# FT232RL.net
KiCad netlist of a schematic drawn in EAGLE
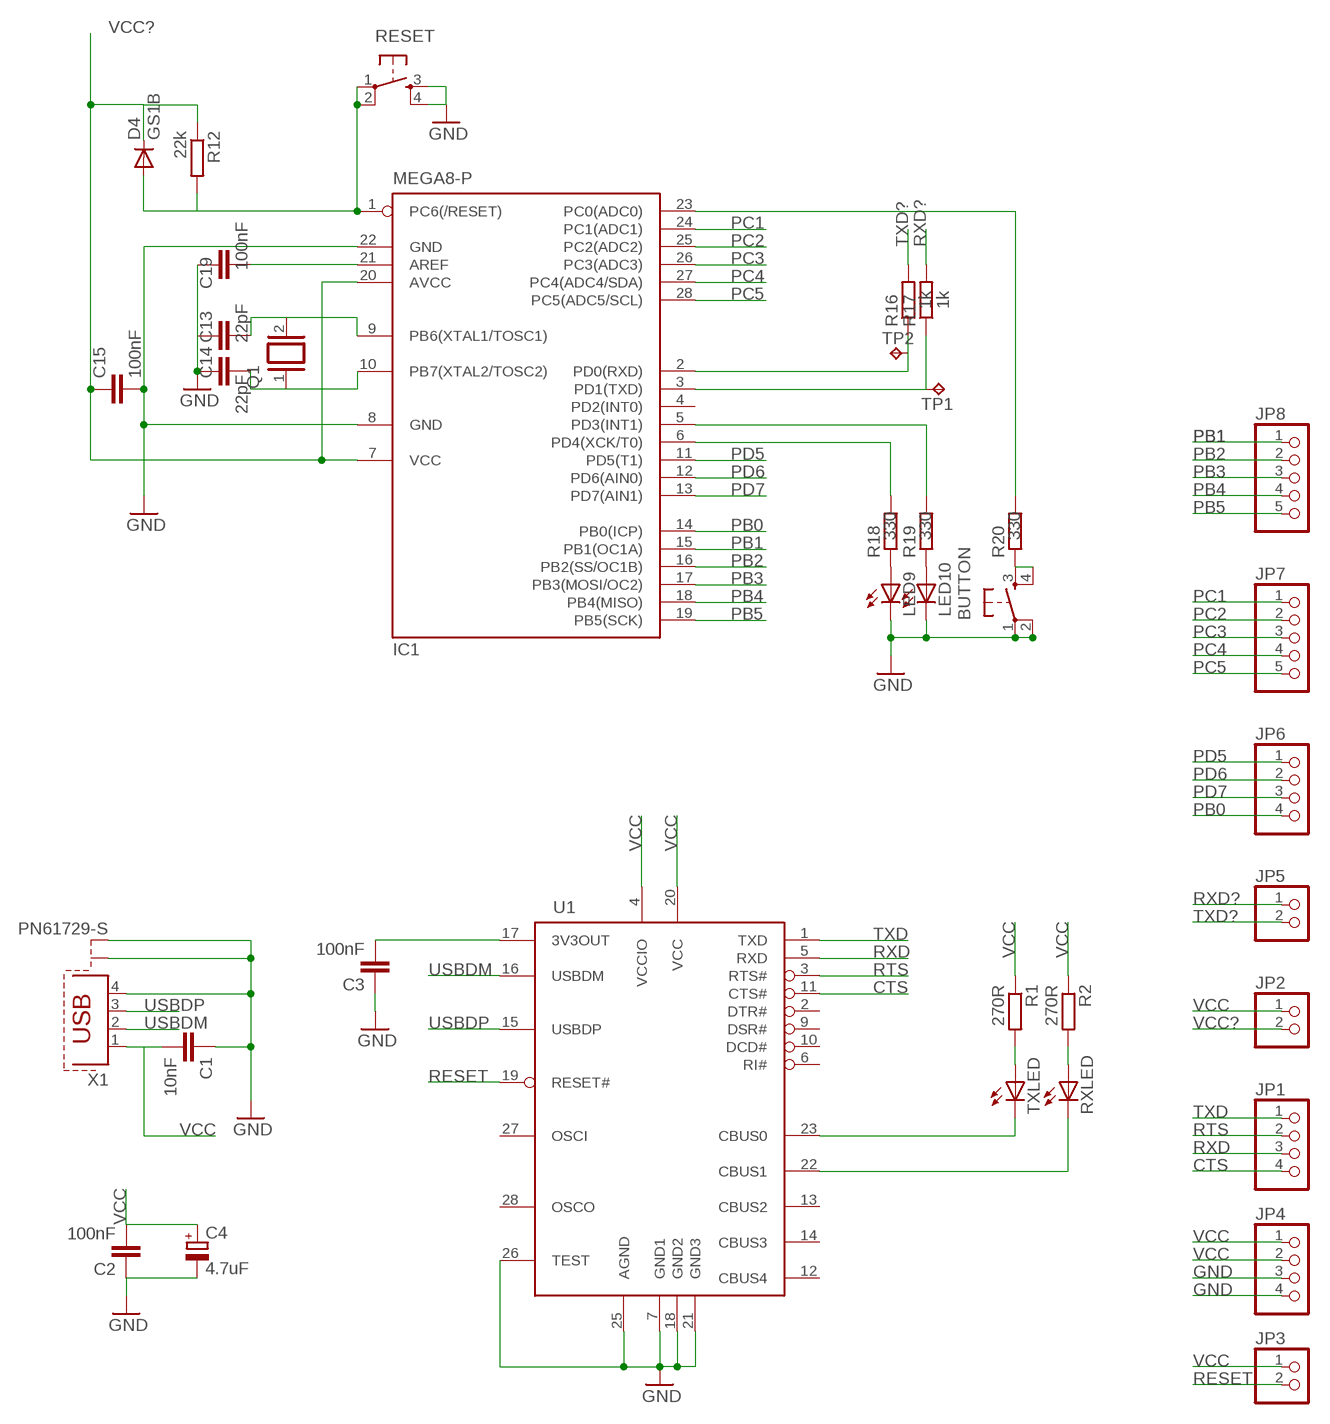
[diagram p0: schematic, sheet 1]

(export (version "E")
  (design (tool "Eeschema 10.0.6"))
  (components
    (comp (ref "BUTTON")
      (value "TAC_SWITCHSMD")
      (footprint "eagle-import:TACTILE_SWITCH_SMD")
      (libsource (lib "eagle-import") (part "TAC_SWITCHSMD"))
    )
    (comp (ref "C1")
      (value "10nF")
      (footprint "eagle-import:C0805")
      (libsource (lib "eagle-import") (part "C-EUC0805"))
    )
    (comp (ref "C2")
      (value "100nF")
      (footprint "eagle-import:C0805")
      (libsource (lib "eagle-import") (part "C-EUC0805"))
    )
    (comp (ref "C3")
      (value "100nF")
      (footprint "eagle-import:C0805")
      (libsource (lib "eagle-import") (part "C-EUC0805"))
    )
    (comp (ref "C4")
      (value "4.7uF")
      (footprint "eagle-import:E1,8-4")
      (libsource (lib "eagle-import") (part "CPOL-EUE1.8-4"))
    )
    (comp (ref "C13")
      (value "22pF")
      (footprint "eagle-import:C0805")
      (libsource (lib "eagle-import") (part "C-EUC0805"))
    )
    (comp (ref "C14")
      (value "22pF")
      (footprint "eagle-import:C0805")
      (libsource (lib "eagle-import") (part "C-EUC0805"))
    )
    (comp (ref "C15")
      (value "100nF")
      (footprint "eagle-import:C0805")
      (libsource (lib "eagle-import") (part "C-EUC0805"))
    )
    (comp (ref "C19")
      (value "100nF")
      (footprint "eagle-import:C0805")
      (libsource (lib "eagle-import") (part "C-EUC0805"))
    )
    (comp (ref "D4")
      (value "GS1B")
      (footprint "eagle-import:DO214AC")
      (libsource (lib "eagle-import") (part "DIODE-DO214AC"))
    )
    (comp (ref "IC1")
      (value "MEGA8-P")
      (footprint "eagle-import:DIL28-3")
      (libsource (lib "eagle-import") (part "MEGA8-P"))
    )
    (comp (ref "JP1")
      (value "PINHD-1X4")
      (footprint "eagle-import:1X04")
      (libsource (lib "eagle-import") (part "PINHD-1X4"))
    )
    (comp (ref "JP2")
      (value "PINHD-1X2")
      (footprint "eagle-import:1X02")
      (libsource (lib "eagle-import") (part "PINHD-1X2"))
    )
    (comp (ref "JP3")
      (value "PINHD-1X2")
      (footprint "eagle-import:1X02")
      (libsource (lib "eagle-import") (part "PINHD-1X2"))
    )
    (comp (ref "JP4")
      (value "PINHD-1X4")
      (footprint "eagle-import:1X04")
      (libsource (lib "eagle-import") (part "PINHD-1X4"))
    )
    (comp (ref "JP5")
      (value "PINHD-1X2")
      (footprint "eagle-import:1X02")
      (libsource (lib "eagle-import") (part "PINHD-1X2"))
    )
    (comp (ref "JP6")
      (value "PINHD-1X4")
      (footprint "eagle-import:1X04")
      (libsource (lib "eagle-import") (part "PINHD-1X4"))
    )
    (comp (ref "JP7")
      (value "PINHD-1X5")
      (footprint "eagle-import:1X05")
      (libsource (lib "eagle-import") (part "PINHD-1X5"))
    )
    (comp (ref "JP8")
      (value "PINHD-1X5")
      (footprint "eagle-import:1X05")
      (libsource (lib "eagle-import") (part "PINHD-1X5"))
    )
    (comp (ref "LED9")
      (value "LEDSMT1206")
      (footprint "eagle-import:1206")
      (libsource (lib "eagle-import") (part "LEDSMT1206"))
    )
    (comp (ref "LED10")
      (value "LEDSMT1206")
      (footprint "eagle-import:1206")
      (libsource (lib "eagle-import") (part "LEDSMT1206"))
    )
    (comp (ref "Q1")
      (value "XTAL")
      (footprint "eagle-import:Q")
      (libsource (lib "eagle-import") (part "XTAL"))
    )
    (comp (ref "R1")
      (value "270R")
      (footprint "eagle-import:R0805")
      (libsource (lib "eagle-import") (part "R-EU_R0805"))
    )
    (comp (ref "R2")
      (value "270R")
      (footprint "eagle-import:R0805")
      (libsource (lib "eagle-import") (part "R-EU_R0805"))
    )
    (comp (ref "R12")
      (value "22k")
      (footprint "eagle-import:R0805")
      (libsource (lib "eagle-import") (part "R-EU_R0805"))
    )
    (comp (ref "R16")
      (value "1k")
      (footprint "eagle-import:R0805")
      (libsource (lib "eagle-import") (part "R-EU_R0805"))
    )
    (comp (ref "R17")
      (value "1k")
      (footprint "eagle-import:R0805")
      (libsource (lib "eagle-import") (part "R-EU_R0805"))
    )
    (comp (ref "R18")
      (value "330")
      (footprint "eagle-import:R0805")
      (libsource (lib "eagle-import") (part "R-EU_R0805"))
    )
    (comp (ref "R19")
      (value "330")
      (footprint "eagle-import:R0805")
      (libsource (lib "eagle-import") (part "R-EU_R0805"))
    )
    (comp (ref "R20")
      (value "330")
      (footprint "eagle-import:R0805")
      (libsource (lib "eagle-import") (part "R-EU_R0805"))
    )
    (comp (ref "RESET")
      (value "TAC_SWITCHSMD")
      (footprint "eagle-import:TACTILE_SWITCH_SMD")
      (libsource (lib "eagle-import") (part "TAC_SWITCHSMD"))
    )
    (comp (ref "RXLED")
      (value "LEDSML1206")
      (footprint "eagle-import:SML1206")
      (libsource (lib "eagle-import") (part "LEDSML1206"))
    )
    (comp (ref "TP1")
      (value "TPTP13R")
      (footprint "eagle-import:TP13R")
      (libsource (lib "eagle-import") (part "TPTP13R"))
    )
    (comp (ref "TP2")
      (value "TPTP13R")
      (footprint "eagle-import:TP13R")
      (libsource (lib "eagle-import") (part "TPTP13R"))
    )
    (comp (ref "TXLED")
      (value "LEDSML1206")
      (footprint "eagle-import:SML1206")
      (libsource (lib "eagle-import") (part "LEDSML1206"))
    )
    (comp (ref "U1")
      (value "FT232RL")
      (footprint "eagle-import:SSOP28DB")
      (libsource (lib "eagle-import") (part "FT232RL"))
    )
    (comp (ref "X1")
      (value "PN61729-S")
      (footprint "eagle-import:PN61729-S")
      (libsource (lib "eagle-import") (part "PN61729-S"))
    )
  )
  (nets
    (net (code "1") (name "/CTS") (class "Default")
      (node (ref "JP1") (pin "4") (pinfunction "4_4") (pintype "passive"))
      (node (ref "U1") (pin "11") (pinfunction "CTS#_11") (pintype "input"))
    )
    (net (code "2") (name "/PB0") (class "Default")
      (node (ref "IC1") (pin "14") (pinfunction "PB0(ICP)_14") (pintype "bidirectional"))
      (node (ref "JP6") (pin "4") (pinfunction "4_4") (pintype "passive"))
    )
    (net (code "3") (name "/PB1") (class "Default")
      (node (ref "IC1") (pin "15") (pinfunction "PB1(OC1A)_15") (pintype "bidirectional"))
      (node (ref "JP8") (pin "1") (pinfunction "1_1") (pintype "passive"))
    )
    (net (code "4") (name "/PB2") (class "Default")
      (node (ref "IC1") (pin "16") (pinfunction "PB2(SS/OC1B)_16") (pintype "bidirectional"))
      (node (ref "JP8") (pin "2") (pinfunction "2_2") (pintype "passive"))
    )
    (net (code "5") (name "/PB3") (class "Default")
      (node (ref "IC1") (pin "17") (pinfunction "PB3(MOSI/OC2)_17") (pintype "bidirectional"))
      (node (ref "JP8") (pin "3") (pinfunction "3_3") (pintype "passive"))
    )
    (net (code "6") (name "/PB4") (class "Default")
      (node (ref "IC1") (pin "18") (pinfunction "PB4(MISO)_18") (pintype "bidirectional"))
      (node (ref "JP8") (pin "4") (pinfunction "4_4") (pintype "passive"))
    )
    (net (code "7") (name "/PB5") (class "Default")
      (node (ref "IC1") (pin "19") (pinfunction "PB5(SCK)_19") (pintype "bidirectional"))
      (node (ref "JP8") (pin "5") (pinfunction "5_5") (pintype "passive"))
    )
    (net (code "8") (name "/PC1") (class "Default")
      (node (ref "IC1") (pin "24") (pinfunction "PC1(ADC1)_24") (pintype "bidirectional"))
      (node (ref "JP7") (pin "1") (pinfunction "1_1") (pintype "passive"))
    )
    (net (code "9") (name "/PC2") (class "Default")
      (node (ref "IC1") (pin "25") (pinfunction "PC2(ADC2)_25") (pintype "bidirectional"))
      (node (ref "JP7") (pin "2") (pinfunction "2_2") (pintype "passive"))
    )
    (net (code "10") (name "/PC3") (class "Default")
      (node (ref "IC1") (pin "26") (pinfunction "PC3(ADC3)_26") (pintype "bidirectional"))
      (node (ref "JP7") (pin "3") (pinfunction "3_3") (pintype "passive"))
    )
    (net (code "11") (name "/PC4") (class "Default")
      (node (ref "IC1") (pin "27") (pinfunction "PC4(ADC4/SDA)_27") (pintype "bidirectional"))
      (node (ref "JP7") (pin "4") (pinfunction "4_4") (pintype "passive"))
    )
    (net (code "12") (name "/PC5") (class "Default")
      (node (ref "IC1") (pin "28") (pinfunction "PC5(ADC5/SCL)_28") (pintype "bidirectional"))
      (node (ref "JP7") (pin "5") (pinfunction "5_5") (pintype "passive"))
    )
    (net (code "13") (name "/PD5") (class "Default")
      (node (ref "IC1") (pin "11") (pinfunction "PD5(T1)_11") (pintype "bidirectional"))
      (node (ref "JP6") (pin "1") (pinfunction "1_1") (pintype "passive"))
    )
    (net (code "14") (name "/PD6") (class "Default")
      (node (ref "IC1") (pin "12") (pinfunction "PD6(AIN0)_12") (pintype "bidirectional"))
      (node (ref "JP6") (pin "2") (pinfunction "2_2") (pintype "passive"))
    )
    (net (code "15") (name "/PD7") (class "Default")
      (node (ref "IC1") (pin "13") (pinfunction "PD7(AIN1)_13") (pintype "bidirectional"))
      (node (ref "JP6") (pin "3") (pinfunction "3_3") (pintype "passive"))
    )
    (net (code "16") (name "/RESET") (class "Default")
      (node (ref "JP3") (pin "2") (pinfunction "2_2") (pintype "passive"))
      (node (ref "U1") (pin "19") (pinfunction "RESET#_19") (pintype "input"))
    )
    (net (code "17") (name "/RTS") (class "Default")
      (node (ref "JP1") (pin "2") (pinfunction "2_2") (pintype "passive"))
      (node (ref "U1") (pin "3") (pinfunction "RTS#_3") (pintype "output"))
    )
    (net (code "18") (name "/RXD") (class "Default")
      (node (ref "JP1") (pin "3") (pinfunction "3_3") (pintype "passive"))
      (node (ref "U1") (pin "5") (pinfunction "RXD_5") (pintype "input"))
    )
    (net (code "19") (name "/RXD?") (class "Default")
      (node (ref "JP5") (pin "1") (pinfunction "1_1") (pintype "passive"))
      (node (ref "R17") (pin "2") (pinfunction "2_2") (pintype "passive"))
    )
    (net (code "20") (name "/TXD") (class "Default")
      (node (ref "JP1") (pin "1") (pinfunction "1_1") (pintype "passive"))
      (node (ref "U1") (pin "1") (pinfunction "TXD_1") (pintype "output"))
    )
    (net (code "21") (name "/TXD?") (class "Default")
      (node (ref "JP5") (pin "2") (pinfunction "2_2") (pintype "passive"))
      (node (ref "R16") (pin "2") (pinfunction "2_2") (pintype "passive"))
    )
    (net (code "22") (name "/USBDM") (class "Default")
      (node (ref "U1") (pin "16") (pinfunction "USBDM_16") (pintype "bidirectional"))
      (node (ref "X1") (pin "2") (pinfunction "2_2") (pintype "passive"))
    )
    (net (code "23") (name "/USBDP") (class "Default")
      (node (ref "U1") (pin "15") (pinfunction "USBDP_15") (pintype "bidirectional"))
      (node (ref "X1") (pin "3") (pinfunction "3_3") (pintype "passive"))
    )
    (net (code "24") (name "/VCC") (class "Default")
      (node (ref "C1") (pin "2") (pinfunction "2_2") (pintype "passive"))
      (node (ref "C2") (pin "2") (pinfunction "2_2") (pintype "passive"))
      (node (ref "C4") (pin "+") (pinfunction "+_+") (pintype "passive"))
      (node (ref "JP2") (pin "1") (pinfunction "1_1") (pintype "passive"))
      (node (ref "JP3") (pin "1") (pinfunction "1_1") (pintype "passive"))
      (node (ref "JP4") (pin "1") (pinfunction "1_1") (pintype "passive"))
      (node (ref "JP4") (pin "2") (pinfunction "2_2") (pintype "passive"))
      (node (ref "R1") (pin "1") (pinfunction "1_1") (pintype "passive"))
      (node (ref "R2") (pin "1") (pinfunction "1_1") (pintype "passive"))
      (node (ref "U1") (pin "20") (pinfunction "VCC_20") (pintype "power_in"))
      (node (ref "U1") (pin "4") (pinfunction "VCCIO_4") (pintype "power_in"))
      (node (ref "X1") (pin "1") (pinfunction "1_1") (pintype "passive"))
    )
    (net (code "25") (name "/VCC?") (class "Default")
      (node (ref "C15") (pin "1") (pinfunction "1_1") (pintype "passive"))
      (node (ref "D4") (pin "C") (pinfunction "C_C") (pintype "passive"))
      (node (ref "IC1") (pin "20") (pinfunction "AVCC_20") (pintype "power_in"))
      (node (ref "IC1") (pin "7") (pinfunction "VCC_7") (pintype "power_in"))
      (node (ref "JP2") (pin "2") (pinfunction "2_2") (pintype "passive"))
      (node (ref "R12") (pin "1") (pinfunction "1_1") (pintype "passive"))
    )
    (net (code "26") (name "GND") (class "Default")
      (node (ref "BUTTON") (pin "1") (pinfunction "1_1") (pintype "passive"))
      (node (ref "BUTTON") (pin "2") (pinfunction "2_2") (pintype "passive"))
      (node (ref "C1") (pin "1") (pinfunction "1_1") (pintype "passive"))
      (node (ref "C13") (pin "1") (pinfunction "1_1") (pintype "passive"))
      (node (ref "C14") (pin "1") (pinfunction "1_1") (pintype "passive"))
      (node (ref "C15") (pin "2") (pinfunction "2_2") (pintype "passive"))
      (node (ref "C19") (pin "2") (pinfunction "2_2") (pintype "passive"))
      (node (ref "C2") (pin "1") (pinfunction "1_1") (pintype "passive"))
      (node (ref "C3") (pin "1") (pinfunction "1_1") (pintype "passive"))
      (node (ref "C4") (pin "-") (pinfunction "-_-") (pintype "passive"))
      (node (ref "IC1") (pin "22") (pinfunction "GND_22") (pintype "power_in"))
      (node (ref "IC1") (pin "8") (pinfunction "GND_8") (pintype "power_in"))
      (node (ref "JP4") (pin "3") (pinfunction "3_3") (pintype "passive"))
      (node (ref "JP4") (pin "4") (pinfunction "4_4") (pintype "passive"))
      (node (ref "LED10") (pin "C") (pinfunction "C_C") (pintype "passive"))
      (node (ref "LED9") (pin "C") (pinfunction "C_C") (pintype "passive"))
      (node (ref "RESET") (pin "3") (pinfunction "3_3") (pintype "passive"))
      (node (ref "RESET") (pin "4") (pinfunction "4_4") (pintype "passive"))
      (node (ref "U1") (pin "18") (pinfunction "GND2_18") (pintype "power_in"))
      (node (ref "U1") (pin "21") (pinfunction "GND3_21") (pintype "power_in"))
      (node (ref "U1") (pin "25") (pinfunction "AGND_25") (pintype "power_in"))
      (node (ref "U1") (pin "26") (pinfunction "TEST_26") (pintype "input"))
      (node (ref "U1") (pin "7") (pinfunction "GND1_7") (pintype "power_in"))
      (node (ref "X1") (pin "4") (pinfunction "4_4") (pintype "passive"))
      (node (ref "X1") (pin "S1") (pinfunction "S1_S1") (pintype "passive"))
      (node (ref "X1") (pin "S2") (pinfunction "S2_S2") (pintype "passive"))
    )
    (net (code "27") (name "Net-(BUTTON-Pad3)") (class "Default")
      (node (ref "BUTTON") (pin "3") (pinfunction "3_3") (pintype "passive"))
      (node (ref "BUTTON") (pin "4") (pinfunction "4_4") (pintype "passive"))
      (node (ref "R20") (pin "1") (pinfunction "1_1") (pintype "passive"))
    )
    (net (code "28") (name "Net-(IC1-AREF)") (class "Default")
      (node (ref "C19") (pin "1") (pinfunction "1_1") (pintype "passive"))
      (node (ref "IC1") (pin "21") (pinfunction "AREF_21") (pintype "passive"))
    )
    (net (code "29") (name "Net-(IC1-PB6(XTAL1{slash}TOSC1))") (class "Default")
      (node (ref "C13") (pin "2") (pinfunction "2_2") (pintype "passive"))
      (node (ref "IC1") (pin "9") (pinfunction "PB6(XTAL1/TOSC1)_9") (pintype "bidirectional"))
      (node (ref "Q1") (pin "2") (pinfunction "2_2") (pintype "passive"))
    )
    (net (code "30") (name "Net-(IC1-PB7(XTAL2{slash}TOSC2))") (class "Default")
      (node (ref "C14") (pin "2") (pinfunction "2_2") (pintype "passive"))
      (node (ref "IC1") (pin "10") (pinfunction "PB7(XTAL2/TOSC2)_10") (pintype "bidirectional"))
      (node (ref "Q1") (pin "1") (pinfunction "1_1") (pintype "passive"))
    )
    (net (code "31") (name "Net-(IC1-PC0(ADC0))") (class "Default")
      (node (ref "IC1") (pin "23") (pinfunction "PC0(ADC0)_23") (pintype "bidirectional"))
      (node (ref "R20") (pin "2") (pinfunction "2_2") (pintype "passive"))
    )
    (net (code "32") (name "Net-(IC1-PC6({slash}RESET))") (class "Default")
      (node (ref "D4") (pin "A") (pinfunction "A_A") (pintype "passive"))
      (node (ref "IC1") (pin "1") (pinfunction "PC6(/RESET)_1") (pintype "bidirectional"))
      (node (ref "R12") (pin "2") (pinfunction "2_2") (pintype "passive"))
      (node (ref "RESET") (pin "1") (pinfunction "1_1") (pintype "passive"))
      (node (ref "RESET") (pin "2") (pinfunction "2_2") (pintype "passive"))
    )
    (net (code "33") (name "Net-(IC1-PD0(RXD))") (class "Default")
      (node (ref "IC1") (pin "2") (pinfunction "PD0(RXD)_2") (pintype "bidirectional"))
      (node (ref "R16") (pin "1") (pinfunction "1_1") (pintype "passive"))
      (node (ref "TP2") (pin "TP") (pinfunction "TP_TP") (pintype "input"))
    )
    (net (code "34") (name "Net-(IC1-PD1(TXD))") (class "Default")
      (node (ref "IC1") (pin "3") (pinfunction "PD1(TXD)_3") (pintype "bidirectional"))
      (node (ref "R17") (pin "1") (pinfunction "1_1") (pintype "passive"))
      (node (ref "TP1") (pin "TP") (pinfunction "TP_TP") (pintype "input"))
    )
    (net (code "35") (name "Net-(IC1-PD3(INT1))") (class "Default")
      (node (ref "IC1") (pin "5") (pinfunction "PD3(INT1)_5") (pintype "bidirectional"))
      (node (ref "R19") (pin "2") (pinfunction "2_2") (pintype "passive"))
    )
    (net (code "36") (name "Net-(IC1-PD4(XCK{slash}T0))") (class "Default")
      (node (ref "IC1") (pin "6") (pinfunction "PD4(XCK/T0)_6") (pintype "bidirectional"))
      (node (ref "R18") (pin "2") (pinfunction "2_2") (pintype "passive"))
    )
    (net (code "37") (name "Net-(LED9-PadA)") (class "Default")
      (node (ref "LED9") (pin "A") (pinfunction "A_A") (pintype "passive"))
      (node (ref "R18") (pin "1") (pinfunction "1_1") (pintype "passive"))
    )
    (net (code "38") (name "Net-(LED10-PadA)") (class "Default")
      (node (ref "LED10") (pin "A") (pinfunction "A_A") (pintype "passive"))
      (node (ref "R19") (pin "1") (pinfunction "1_1") (pintype "passive"))
    )
    (net (code "39") (name "Net-(R1-Pad2)") (class "Default")
      (node (ref "R1") (pin "2") (pinfunction "2_2") (pintype "passive"))
      (node (ref "TXLED") (pin "A") (pinfunction "A_A") (pintype "passive"))
    )
    (net (code "40") (name "Net-(R2-Pad2)") (class "Default")
      (node (ref "R2") (pin "2") (pinfunction "2_2") (pintype "passive"))
      (node (ref "RXLED") (pin "A") (pinfunction "A_A") (pintype "passive"))
    )
    (net (code "41") (name "Net-(U1-3V3OUT)") (class "Default")
      (node (ref "C3") (pin "2") (pinfunction "2_2") (pintype "passive"))
      (node (ref "U1") (pin "17") (pinfunction "3V3OUT_17") (pintype "output"))
    )
    (net (code "42") (name "Net-(U1-CBUS0)") (class "Default")
      (node (ref "TXLED") (pin "C") (pinfunction "C_C") (pintype "passive"))
      (node (ref "U1") (pin "23") (pinfunction "CBUS0_23") (pintype "bidirectional"))
    )
    (net (code "43") (name "Net-(U1-CBUS1)") (class "Default")
      (node (ref "RXLED") (pin "C") (pinfunction "C_C") (pintype "passive"))
      (node (ref "U1") (pin "22") (pinfunction "CBUS1_22") (pintype "bidirectional"))
    )
    (net (code "44") (name "unconnected-(IC1-PD2(INT0)-Pad4)") (class "Default")
      (node (ref "IC1") (pin "4") (pinfunction "PD2(INT0)_4") (pintype "bidirectional"))
    )
    (net (code "45") (name "unconnected-(U1-CBUS2-Pad13)") (class "Default")
      (node (ref "U1") (pin "13") (pinfunction "CBUS2_13") (pintype "bidirectional"))
    )
    (net (code "46") (name "unconnected-(U1-CBUS3-Pad14)") (class "Default")
      (node (ref "U1") (pin "14") (pinfunction "CBUS3_14") (pintype "bidirectional"))
    )
    (net (code "47") (name "unconnected-(U1-CBUS4-Pad12)") (class "Default")
      (node (ref "U1") (pin "12") (pinfunction "CBUS4_12") (pintype "bidirectional"))
    )
    (net (code "48") (name "unconnected-(U1-DCD#-Pad10)") (class "Default")
      (node (ref "U1") (pin "10") (pinfunction "DCD#_10") (pintype "input"))
    )
    (net (code "49") (name "unconnected-(U1-DSR#-Pad9)") (class "Default")
      (node (ref "U1") (pin "9") (pinfunction "DSR#_9") (pintype "input"))
    )
    (net (code "50") (name "unconnected-(U1-DTR#-Pad2)") (class "Default")
      (node (ref "U1") (pin "2") (pinfunction "DTR#_2") (pintype "output"))
    )
    (net (code "51") (name "unconnected-(U1-OSCI-Pad27)") (class "Default")
      (node (ref "U1") (pin "27") (pinfunction "OSCI_27") (pintype "input"))
    )
    (net (code "52") (name "unconnected-(U1-OSCO-Pad28)") (class "Default")
      (node (ref "U1") (pin "28") (pinfunction "OSCO_28") (pintype "output"))
    )
    (net (code "53") (name "unconnected-(U1-RI#-Pad6)") (class "Default")
      (node (ref "U1") (pin "6") (pinfunction "RI#_6") (pintype "input"))
    )
  )
)
